# TapuinoNext.net
KiCad netlist of a schematic drawn in EAGLE
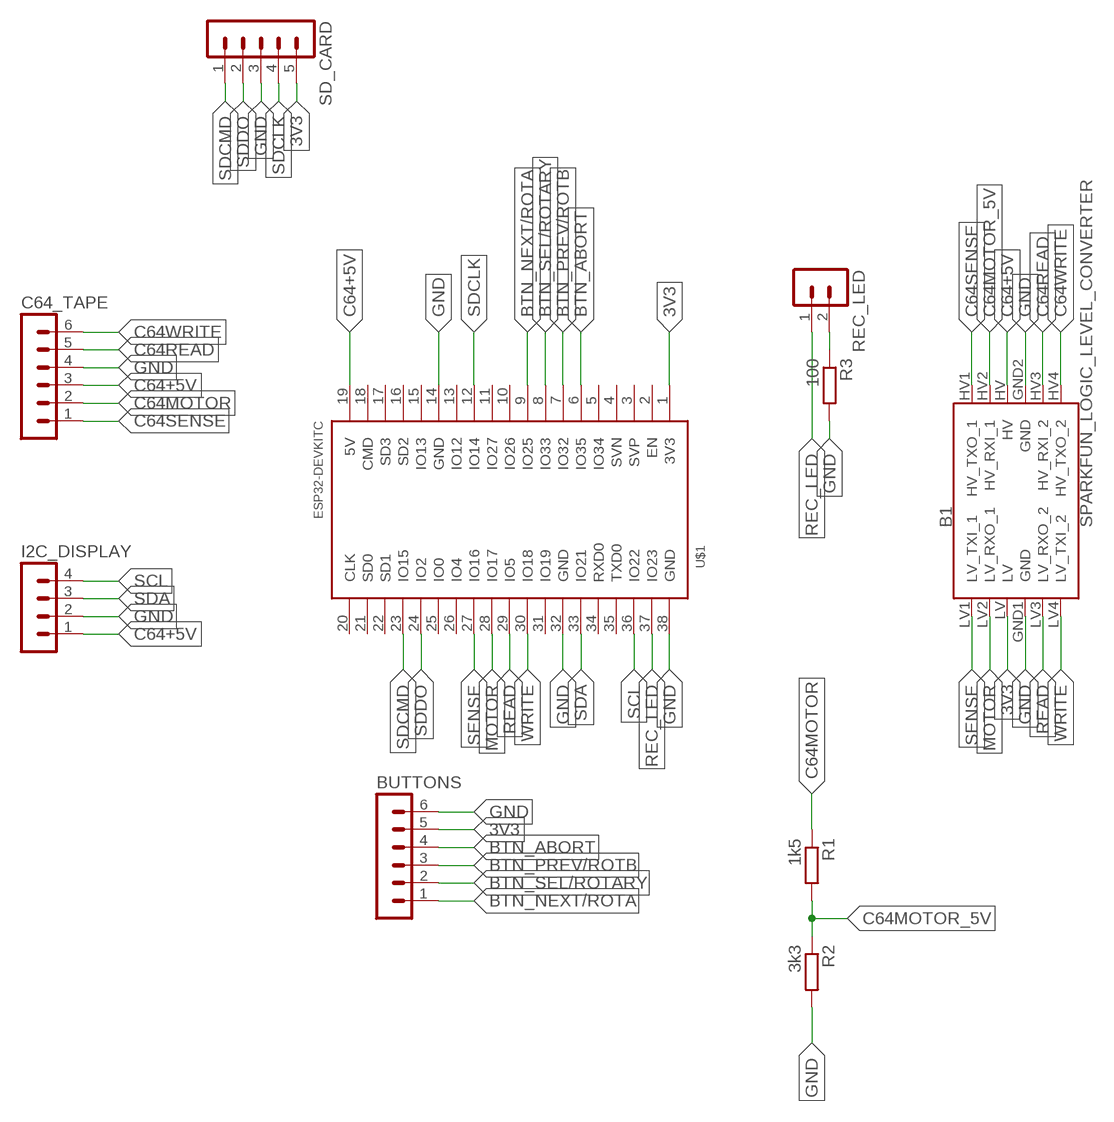
[diagram p0: schematic, sheet 1]

(export (version "E")
  (design (tool "Eeschema 10.0.6"))
  (components
    (comp (ref "B1")
      (value "SPARKFUN_LOGIC_LEVEL_CONVERTER")
      (footprint "eagle-import:SPARKFUN_LOGIC_LEVEL_CONVERTER")
      (libsource (lib "eagle-import") (part "SPARKFUN_LOGIC_LEVEL_CONVERTER"))
    )
    (comp (ref "BUTTONS")
      (value "MA06-1")
      (footprint "eagle-import:MA06-1")
      (libsource (lib "eagle-import") (part "MA06-1"))
    )
    (comp (ref "C64_TAPE")
      (value "MA06-1")
      (footprint "eagle-import:MA06-1")
      (libsource (lib "eagle-import") (part "MA06-1"))
    )
    (comp (ref "I2C_DISPLAY")
      (value "MA04-1")
      (footprint "eagle-import:MA04-1")
      (libsource (lib "eagle-import") (part "MA04-1"))
    )
    (comp (ref "R1")
      (value "1k5")
      (footprint "eagle-import:0204_7")
      (libsource (lib "eagle-import") (part "R-EU_0204/7"))
    )
    (comp (ref "R2")
      (value "3k3")
      (footprint "eagle-import:0204_7")
      (libsource (lib "eagle-import") (part "R-EU_0204/7"))
    )
    (comp (ref "R3")
      (value "100")
      (footprint "eagle-import:0204_7")
      (libsource (lib "eagle-import") (part "R-EU_0204/7"))
    )
    (comp (ref "REC_LED")
      (value "MA02-1")
      (footprint "eagle-import:MA02-1")
      (libsource (lib "eagle-import") (part "MA02-1"))
    )
    (comp (ref "SD_CARD")
      (value "MA05-1")
      (footprint "eagle-import:MA05-1")
      (libsource (lib "eagle-import") (part "MA05-1"))
    )
    (comp (ref "U$1")
      (value "ESP32DEVKITC")
      (footprint "eagle-import:ESP32-DEVKITC")
      (libsource (lib "eagle-import") (part "ESP32DEVKITC"))
    )
  )
  (nets
    (net (code "1") (name "3V3") (class "Default")
      (node (ref "B1") (pin "LV") (pinfunction "LV_LV") (pintype "power_in"))
      (node (ref "BUTTONS") (pin "5") (pinfunction "5_5") (pintype "passive"))
      (node (ref "SD_CARD") (pin "5") (pinfunction "5_5") (pintype "passive"))
      (node (ref "U$1") (pin "1") (pinfunction "3V3_1") (pintype "bidirectional"))
    )
    (net (code "2") (name "BTN_ABORT") (class "Default")
      (node (ref "BUTTONS") (pin "4") (pinfunction "4_4") (pintype "passive"))
      (node (ref "U$1") (pin "6") (pinfunction "IO35_6") (pintype "bidirectional"))
    )
    (net (code "3") (name "BTN_NEXT{slash}ROTA") (class "Default")
      (node (ref "BUTTONS") (pin "1") (pinfunction "1_1") (pintype "passive"))
      (node (ref "U$1") (pin "9") (pinfunction "IO25_9") (pintype "bidirectional"))
    )
    (net (code "4") (name "BTN_PREV{slash}ROTB") (class "Default")
      (node (ref "BUTTONS") (pin "3") (pinfunction "3_3") (pintype "passive"))
      (node (ref "U$1") (pin "7") (pinfunction "IO32_7") (pintype "bidirectional"))
    )
    (net (code "5") (name "BTN_SEL{slash}ROTARY") (class "Default")
      (node (ref "BUTTONS") (pin "2") (pinfunction "2_2") (pintype "passive"))
      (node (ref "U$1") (pin "8") (pinfunction "IO33_8") (pintype "bidirectional"))
    )
    (net (code "6") (name "C64+5V") (class "Default")
      (node (ref "B1") (pin "HV") (pinfunction "HV_HV") (pintype "power_in"))
      (node (ref "C64_TAPE") (pin "3") (pinfunction "3_3") (pintype "passive"))
      (node (ref "I2C_DISPLAY") (pin "1") (pinfunction "1_1") (pintype "passive"))
      (node (ref "U$1") (pin "19") (pinfunction "5V_19") (pintype "bidirectional"))
    )
    (net (code "7") (name "C64MOTOR") (class "Default")
      (node (ref "C64_TAPE") (pin "2") (pinfunction "2_2") (pintype "passive"))
      (node (ref "R1") (pin "1") (pinfunction "1_1") (pintype "passive"))
    )
    (net (code "8") (name "C64MOTOR_5V") (class "Default")
      (node (ref "B1") (pin "HV2") (pinfunction "HV_RXI_1_HV2") (pintype "bidirectional"))
      (node (ref "R1") (pin "2") (pinfunction "2_2") (pintype "passive"))
      (node (ref "R2") (pin "1") (pinfunction "1_1") (pintype "passive"))
    )
    (net (code "9") (name "C64READ") (class "Default")
      (node (ref "B1") (pin "HV3") (pinfunction "HV_RXI_2_HV3") (pintype "bidirectional"))
      (node (ref "C64_TAPE") (pin "5") (pinfunction "5_5") (pintype "passive"))
    )
    (net (code "10") (name "C64SENSE") (class "Default")
      (node (ref "B1") (pin "HV1") (pinfunction "HV_TXO_1_HV1") (pintype "bidirectional"))
      (node (ref "C64_TAPE") (pin "1") (pinfunction "1_1") (pintype "passive"))
    )
    (net (code "11") (name "C64WRITE") (class "Default")
      (node (ref "B1") (pin "HV4") (pinfunction "HV_TXO_2_HV4") (pintype "bidirectional"))
      (node (ref "C64_TAPE") (pin "6") (pinfunction "6_6") (pintype "passive"))
    )
    (net (code "12") (name "GND") (class "Default")
      (node (ref "B1") (pin "GND1") (pinfunction "GND_GND1") (pintype "power_in"))
      (node (ref "B1") (pin "GND2") (pinfunction "GND_GND2") (pintype "power_in"))
      (node (ref "BUTTONS") (pin "6") (pinfunction "6_6") (pintype "passive"))
      (node (ref "C64_TAPE") (pin "4") (pinfunction "4_4") (pintype "passive"))
      (node (ref "I2C_DISPLAY") (pin "2") (pinfunction "2_2") (pintype "passive"))
      (node (ref "R2") (pin "2") (pinfunction "2_2") (pintype "passive"))
      (node (ref "R3") (pin "2") (pinfunction "2_2") (pintype "passive"))
      (node (ref "SD_CARD") (pin "3") (pinfunction "3_3") (pintype "passive"))
      (node (ref "U$1") (pin "14") (pinfunction "GND_14") (pintype "bidirectional"))
      (node (ref "U$1") (pin "32") (pinfunction "GND_32") (pintype "bidirectional"))
      (node (ref "U$1") (pin "38") (pinfunction "GND_38") (pintype "bidirectional"))
    )
    (net (code "13") (name "MOTOR") (class "Default")
      (node (ref "B1") (pin "LV2") (pinfunction "LV_RXO_1_LV2") (pintype "bidirectional"))
      (node (ref "U$1") (pin "28") (pinfunction "IO17_28") (pintype "bidirectional"))
    )
    (net (code "14") (name "Net-(R3-Pad1)") (class "Default")
      (node (ref "R3") (pin "1") (pinfunction "1_1") (pintype "passive"))
      (node (ref "REC_LED") (pin "2") (pinfunction "2_2") (pintype "passive"))
    )
    (net (code "15") (name "READ") (class "Default")
      (node (ref "B1") (pin "LV3") (pinfunction "LV_RXO_2_LV3") (pintype "bidirectional"))
      (node (ref "U$1") (pin "29") (pinfunction "IO5_29") (pintype "bidirectional"))
    )
    (net (code "16") (name "REC_LED") (class "Default")
      (node (ref "REC_LED") (pin "1") (pinfunction "1_1") (pintype "passive"))
      (node (ref "U$1") (pin "37") (pinfunction "IO23_37") (pintype "bidirectional"))
    )
    (net (code "17") (name "SCL") (class "Default")
      (node (ref "I2C_DISPLAY") (pin "4") (pinfunction "4_4") (pintype "passive"))
      (node (ref "U$1") (pin "36") (pinfunction "IO22_36") (pintype "bidirectional"))
    )
    (net (code "18") (name "SDA") (class "Default")
      (node (ref "I2C_DISPLAY") (pin "3") (pinfunction "3_3") (pintype "passive"))
      (node (ref "U$1") (pin "33") (pinfunction "IO21_33") (pintype "bidirectional"))
    )
    (net (code "19") (name "SDCLK") (class "Default")
      (node (ref "SD_CARD") (pin "4") (pinfunction "4_4") (pintype "passive"))
      (node (ref "U$1") (pin "12") (pinfunction "IO14_12") (pintype "bidirectional"))
    )
    (net (code "20") (name "SDCMD") (class "Default")
      (node (ref "SD_CARD") (pin "1") (pinfunction "1_1") (pintype "passive"))
      (node (ref "U$1") (pin "23") (pinfunction "IO15_23") (pintype "bidirectional"))
    )
    (net (code "21") (name "SDDO") (class "Default")
      (node (ref "SD_CARD") (pin "2") (pinfunction "2_2") (pintype "passive"))
      (node (ref "U$1") (pin "24") (pinfunction "IO2_24") (pintype "bidirectional"))
    )
    (net (code "22") (name "SENSE") (class "Default")
      (node (ref "B1") (pin "LV1") (pinfunction "LV_TXI_1_LV1") (pintype "bidirectional"))
      (node (ref "U$1") (pin "27") (pinfunction "IO16_27") (pintype "bidirectional"))
    )
    (net (code "23") (name "WRITE") (class "Default")
      (node (ref "B1") (pin "LV4") (pinfunction "LV_TXI_2_LV4") (pintype "bidirectional"))
      (node (ref "U$1") (pin "30") (pinfunction "IO18_30") (pintype "bidirectional"))
    )
    (net (code "24") (name "unconnected-(U$1-CLK-Pad20)") (class "Default")
      (node (ref "U$1") (pin "20") (pinfunction "CLK_20") (pintype "bidirectional"))
    )
    (net (code "25") (name "unconnected-(U$1-CMD-Pad18)") (class "Default")
      (node (ref "U$1") (pin "18") (pinfunction "CMD_18") (pintype "bidirectional"))
    )
    (net (code "26") (name "unconnected-(U$1-EN-Pad2)") (class "Default")
      (node (ref "U$1") (pin "2") (pinfunction "EN_2") (pintype "bidirectional"))
    )
    (net (code "27") (name "unconnected-(U$1-IO0-Pad25)") (class "Default")
      (node (ref "U$1") (pin "25") (pinfunction "IO0_25") (pintype "bidirectional"))
    )
    (net (code "28") (name "unconnected-(U$1-IO4-Pad26)") (class "Default")
      (node (ref "U$1") (pin "26") (pinfunction "IO4_26") (pintype "bidirectional"))
    )
    (net (code "29") (name "unconnected-(U$1-IO12-Pad13)") (class "Default")
      (node (ref "U$1") (pin "13") (pinfunction "IO12_13") (pintype "bidirectional"))
    )
    (net (code "30") (name "unconnected-(U$1-IO13-Pad15)") (class "Default")
      (node (ref "U$1") (pin "15") (pinfunction "IO13_15") (pintype "bidirectional"))
    )
    (net (code "31") (name "unconnected-(U$1-IO19-Pad31)") (class "Default")
      (node (ref "U$1") (pin "31") (pinfunction "IO19_31") (pintype "bidirectional"))
    )
    (net (code "32") (name "unconnected-(U$1-IO26-Pad10)") (class "Default")
      (node (ref "U$1") (pin "10") (pinfunction "IO26_10") (pintype "bidirectional"))
    )
    (net (code "33") (name "unconnected-(U$1-IO27-Pad11)") (class "Default")
      (node (ref "U$1") (pin "11") (pinfunction "IO27_11") (pintype "bidirectional"))
    )
    (net (code "34") (name "unconnected-(U$1-IO34-Pad5)") (class "Default")
      (node (ref "U$1") (pin "5") (pinfunction "IO34_5") (pintype "bidirectional"))
    )
    (net (code "35") (name "unconnected-(U$1-RXD0-Pad34)") (class "Default")
      (node (ref "U$1") (pin "34") (pinfunction "RXD0_34") (pintype "bidirectional"))
    )
    (net (code "36") (name "unconnected-(U$1-SD0-Pad21)") (class "Default")
      (node (ref "U$1") (pin "21") (pinfunction "SD0_21") (pintype "bidirectional"))
    )
    (net (code "37") (name "unconnected-(U$1-SD1-Pad22)") (class "Default")
      (node (ref "U$1") (pin "22") (pinfunction "SD1_22") (pintype "bidirectional"))
    )
    (net (code "38") (name "unconnected-(U$1-SD2-Pad16)") (class "Default")
      (node (ref "U$1") (pin "16") (pinfunction "SD2_16") (pintype "bidirectional"))
    )
    (net (code "39") (name "unconnected-(U$1-SD3-Pad17)") (class "Default")
      (node (ref "U$1") (pin "17") (pinfunction "SD3_17") (pintype "bidirectional"))
    )
    (net (code "40") (name "unconnected-(U$1-SVN-Pad4)") (class "Default")
      (node (ref "U$1") (pin "4") (pinfunction "SVN_4") (pintype "bidirectional"))
    )
    (net (code "41") (name "unconnected-(U$1-SVP-Pad3)") (class "Default")
      (node (ref "U$1") (pin "3") (pinfunction "SVP_3") (pintype "bidirectional"))
    )
    (net (code "42") (name "unconnected-(U$1-TXD0-Pad35)") (class "Default")
      (node (ref "U$1") (pin "35") (pinfunction "TXD0_35") (pintype "bidirectional"))
    )
  )
)
